# TNY276PN_5V_800mA_SMPS.net
KiCad netlist of a schematic drawn in Altium Designer
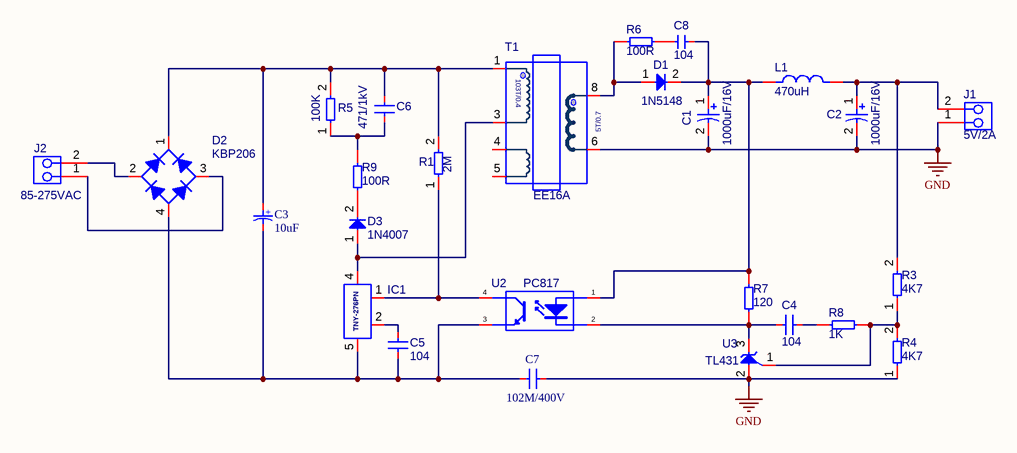
[diagram p0: TNY276PN_5V_800mA_SMPS.SchDoc]

(export (version "E")
  (design (tool "Eeschema 10.0.6"))
  (components
    (comp (ref "C1")
      (value "1000uF/16V")
      (footprint "CAP_RAD_3.5mm")
      (libsource (lib "Lib31082020") (part "Capacitor(Radian)"))
    )
    (comp (ref "C2")
      (value "1000uF/16V")
      (footprint "CAP_RAD_3.5mm")
      (libsource (lib "Lib31082020") (part "Capacitor(Radian)"))
    )
    (comp (ref "C3")
      (value "10uF")
      (footprint "CAP_RAD_D10x12.5_POL_BK")
      (libsource (lib "MyAltiumLibrary") (part "Capacitor(Radian)"))
    )
    (comp (ref "C4")
      (value "104")
      (footprint "CAP_DISC_4x3_YL")
      (libsource (lib "MyAltiumLibrary") (part "Capacitors(Disc)"))
    )
    (comp (ref "C5")
      (value "104")
      (footprint "CAP_DISC_104")
      (libsource (lib "MyAltiumLibrary") (part "Capacitors(Disc)"))
    )
    (comp (ref "C6")
      (value "471/1kV")
      (footprint "CAP_DISC_4x3_YL")
      (libsource (lib "MyAltiumLibrary") (part "Capacitors(Disc)"))
    )
    (comp (ref "C7")
      (value "102M/400V")
      (footprint "CAP_DISC_Y2222")
      (libsource (lib "MyAltiumLibrary") (part "Capacitors(Disc)"))
    )
    (comp (ref "C8")
      (value "104")
      (footprint "CAP_Ceramic_Disc_2")
      (libsource (lib "") (part "Capacitors(Disc)_1"))
    )
    (comp (ref "D1")
      (value "1N5148")
      (footprint "DO-41")
      (libsource (lib "MyAltiumLibrary") (part "Diode-1N4007"))
    )
    (comp (ref "D2")
      (value "KBP206")
      (footprint "DIODE-KBP206")
      (libsource (lib "MyAltiumLibrary") (part "Diode-KBP206"))
    )
    (comp (ref "D3")
      (value "1N4007")
      (footprint "DO-41")
      (libsource (lib "MyAltiumLibrary") (part "Diode-1N4007"))
    )
    (comp (ref "IC1")
      (value "TNY-276PN")
      (footprint "TNY-276PN-DIP-8C")
      (description "TinySwitch-III Family")
      (libsource (lib "MyAltiumLibrary") (part "SMPS-TNY276PN"))
    )
    (comp (ref "J1")
      (value "5V/2A")
      (footprint "DG306-5.0-02P-12-00AH")
      (libsource (lib "Lib31082020") (part "DG306-5.0-02P-12-00AH"))
    )
    (comp (ref "J2")
      (value "85-275VAC")
      (footprint "DG127-5.0-02P-14-00AH")
      (libsource (lib "Lib31082020") (part "DG127-5.0-02P-14-00AH"))
    )
    (comp (ref "L1")
      (value "470uH")
      (footprint "RLB0812_vertical")
      (libsource (lib "MyAltiumLibrary") (part "Inductors"))
    )
    (comp (ref "R1")
      (value "2M")
      (footprint "RES-0.25W-H-MF")
      (libsource (lib "Lib31082020") (part "Resistors THD"))
    )
    (comp (ref "R3")
      (value "4K7")
      (footprint "RES-0.25W-H-MF")
      (libsource (lib "Lib31082020") (part "Resistors THD"))
    )
    (comp (ref "R4")
      (value "4K7")
      (footprint "RES-0.25W-H-MF")
      (libsource (lib "Lib31082020") (part "Resistors THD"))
    )
    (comp (ref "R5")
      (value "100K")
      (footprint "RES-0.25W-H-MF")
      (libsource (lib "Lib31082020") (part "Resistors THD"))
    )
    (comp (ref "R6")
      (value "100R")
      (footprint "RES-0.25W-H-MF")
      (libsource (lib "MyAltiumLibrary") (part "Resistors THD"))
    )
    (comp (ref "R7") (value "120") (footprint "RES-0.25W-H-MF") (libsource (lib "") (part "Resistors THD_2")))
    (comp (ref "R8") (value "1K") (footprint "RES-0.25W-H-MF") (libsource (lib "") (part "Resistors THD_1")))
    (comp (ref "R9")
      (value "100R")
      (footprint "RES-0.25W-H-MF")
      (libsource (lib "") (part "Resistors THD_2"))
    )
    (comp (ref "T1")
      (value "EE16A")
      (footprint "TRANSFORMER-EE16A")
      (libsource (lib "MyAltiumLibrary") (part "TRANS-EE16A-ATX-VERTICAL"))
    )
    (comp (ref "U2") (value "PC817") (footprint "DIP4") (libsource (lib "Lib31082020") (part "PC817")))
    (comp (ref "U3") (value "TL431") (footprint "TO-92") (libsource (lib "Lib31082020") (part "TL431")))
  )
  (nets
    (net (code "1") (name "GND") (class "Default")
      (node (ref "C1") (pin "2") (pinfunction "2_2") (pintype "passive"))
      (node (ref "C2") (pin "2") (pinfunction "2_2") (pintype "passive"))
      (node (ref "C7") (pin "2") (pinfunction "2_2") (pintype "passive"))
      (node (ref "J1") (pin "1") (pinfunction "1_1") (pintype "passive"))
      (node (ref "R4") (pin "1") (pinfunction "1_1") (pintype "passive"))
      (node (ref "T1") (pin "6") (pinfunction "6_6") (pintype "passive"))
      (node (ref "U3") (pin "2") (pinfunction "2_2") (pintype "passive"))
    )
    (net (code "2") (name "Net-(C2-Pad1)") (class "Default")
      (node (ref "C2") (pin "1") (pinfunction "1_1") (pintype "passive"))
      (node (ref "J1") (pin "2") (pinfunction "2_2") (pintype "passive"))
      (node (ref "L1") (pin "2") (pinfunction "2_2") (pintype "passive"))
      (node (ref "R3") (pin "2") (pinfunction "2_2") (pintype "passive"))
    )
    (net (code "3") (name "Net-(C4-Pad1)") (class "Default")
      (node (ref "C4") (pin "1") (pinfunction "1_1") (pintype "passive"))
      (node (ref "R8") (pin "2") (pinfunction "2_2") (pintype "passive"))
    )
    (net (code "4") (name "Net-(C5-Pad2)") (class "Default")
      (node (ref "C5") (pin "2") (pinfunction "2_2") (pintype "passive"))
      (node (ref "IC1") (pin "2") (pinfunction "2_2") (pintype "passive"))
    )
    (net (code "5") (name "Net-(C6-Pad1)") (class "Default")
      (node (ref "C6") (pin "1") (pinfunction "1_1") (pintype "passive"))
      (node (ref "R5") (pin "1") (pinfunction "1_1") (pintype "passive"))
      (node (ref "R9") (pin "2") (pinfunction "2_2") (pintype "passive"))
    )
    (net (code "6") (name "Net-(C8-Pad1)") (class "Default")
      (node (ref "C8") (pin "1") (pinfunction "1_1") (pintype "passive"))
      (node (ref "R6") (pin "2") (pinfunction "2_2") (pintype "passive"))
    )
    (net (code "7") (name "Net-(D1-Pad1)") (class "Default")
      (node (ref "D1") (pin "1") (pinfunction "1_1") (pintype "passive"))
      (node (ref "R6") (pin "1") (pinfunction "1_1") (pintype "passive"))
      (node (ref "T1") (pin "8") (pinfunction "8_8") (pintype "passive"))
    )
    (net (code "8") (name "Net-(D2-+)") (class "Default")
      (node (ref "C3") (pin "1") (pinfunction "1_1") (pintype "passive"))
      (node (ref "C6") (pin "2") (pinfunction "2_2") (pintype "passive"))
      (node (ref "D2") (pin "1") (pinfunction "+_1") (pintype "passive"))
      (node (ref "R1") (pin "2") (pinfunction "2_2") (pintype "passive"))
      (node (ref "R5") (pin "2") (pinfunction "2_2") (pintype "passive"))
      (node (ref "T1") (pin "1") (pinfunction "1_1") (pintype "passive"))
    )
    (net (code "9") (name "Net-(D2--)") (class "Default")
      (node (ref "C3") (pin "2") (pinfunction "2_2") (pintype "passive"))
      (node (ref "C5") (pin "1") (pinfunction "1_1") (pintype "passive"))
      (node (ref "C7") (pin "1") (pinfunction "1_1") (pintype "passive"))
      (node (ref "D2") (pin "4") (pinfunction "-_4") (pintype "passive"))
      (node (ref "IC1") (pin "5") (pinfunction "5_5") (pintype "passive"))
      (node (ref "U2") (pin "3") (pinfunction "E_3") (pintype "passive"))
    )
    (net (code "10") (name "Net-(D2-AC-Pad2)") (class "Default")
      (node (ref "D2") (pin "2") (pinfunction "AC_2") (pintype "passive"))
      (node (ref "J2") (pin "2") (pinfunction "2_2") (pintype "passive"))
    )
    (net (code "11") (name "Net-(D2-AC-Pad3)") (class "Default")
      (node (ref "D2") (pin "3") (pinfunction "AC_3") (pintype "passive"))
      (node (ref "J2") (pin "1") (pinfunction "1_1") (pintype "passive"))
    )
    (net (code "12") (name "Net-(D3-Pad1)") (class "Default")
      (node (ref "D3") (pin "1") (pinfunction "1_1") (pintype "passive"))
      (node (ref "IC1") (pin "4") (pinfunction "4_4") (pintype "passive"))
      (node (ref "T1") (pin "3") (pinfunction "3_3") (pintype "passive"))
    )
    (net (code "13") (name "Net-(D3-Pad2)") (class "Default")
      (node (ref "D3") (pin "2") (pinfunction "2_2") (pintype "passive"))
      (node (ref "R9") (pin "1") (pinfunction "1_1") (pintype "passive"))
    )
    (net (code "14") (name "Net-(R3-Pad1)") (class "Default")
      (node (ref "R3") (pin "1") (pinfunction "1_1") (pintype "passive"))
      (node (ref "R4") (pin "2") (pinfunction "2_2") (pintype "passive"))
      (node (ref "R8") (pin "1") (pinfunction "1_1") (pintype "passive"))
      (node (ref "U3") (pin "1") (pinfunction "1_1") (pintype "passive"))
    )
    (net (code "15") (name "Net-(U2-A)") (class "Default")
      (node (ref "C1") (pin "1") (pinfunction "1_1") (pintype "passive"))
      (node (ref "C8") (pin "2") (pinfunction "2_2") (pintype "passive"))
      (node (ref "D1") (pin "2") (pinfunction "2_2") (pintype "passive"))
      (node (ref "L1") (pin "1") (pinfunction "1_1") (pintype "passive"))
      (node (ref "R7") (pin "2") (pinfunction "2_2") (pintype "passive"))
      (node (ref "U2") (pin "1") (pinfunction "A_1") (pintype "passive"))
    )
    (net (code "16") (name "Net-(U2-C)") (class "Default")
      (node (ref "IC1") (pin "1") (pinfunction "1_1") (pintype "passive"))
      (node (ref "R1") (pin "1") (pinfunction "1_1") (pintype "passive"))
      (node (ref "U2") (pin "4") (pinfunction "C_4") (pintype "passive"))
    )
    (net (code "17") (name "Net-(U2-K)") (class "Default")
      (node (ref "C4") (pin "2") (pinfunction "2_2") (pintype "passive"))
      (node (ref "R7") (pin "1") (pinfunction "1_1") (pintype "passive"))
      (node (ref "U2") (pin "2") (pinfunction "K_2") (pintype "passive"))
      (node (ref "U3") (pin "3") (pinfunction "3_3") (pintype "passive"))
    )
    (net (code "18") (name "unconnected-(T1-Pad4)") (class "Default")
      (node (ref "T1") (pin "4") (pinfunction "4_4") (pintype "passive"))
    )
    (net (code "19") (name "unconnected-(T1-Pad5)") (class "Default")
      (node (ref "T1") (pin "5") (pinfunction "5_5") (pintype "passive"))
    )
  )
)
